# airsensor.net
KiCad netlist of a schematic drawn in Altium Designer
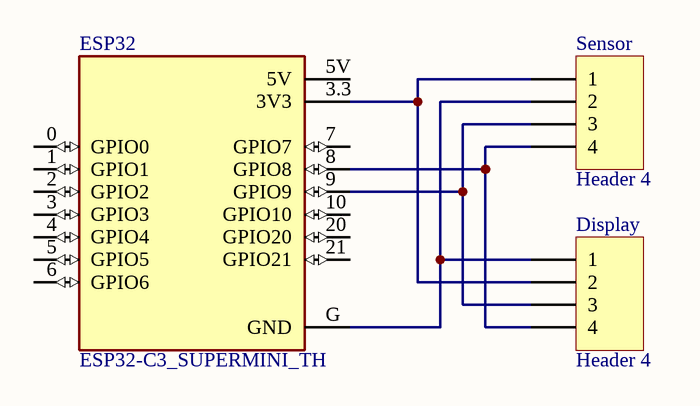
[diagram p0: airsensor.SchDoc]

(export (version "E")
  (design (tool "Eeschema 10.0.6"))
  (components
    (comp (ref "Display")
      (value "Header 4")
      (footprint "HDR1X4")
      (description "Header, 4-Pin")
      (fields (field (name "PUBLISHER") "Altium Limited"))
      (libsource (lib "Miscellaneous Connectors") (part "Header 4"))
    )
    (comp (ref "ESP32")
      (value "ESP32-C3_SUPERMINI_TH")
      (footprint "MODULE_ESP32-C3_SUPERMINI")
      (description "Super tiny ESP32-C3 board")
      (fields (field (name "MF") "Espressif Systems") (field (name "MP") "ESP32-C3 SuperMini_TH"))
      (libsource (lib "ESP32-C3_SUPERMINI_TH") (part "ESP32-C3_SUPERMINI_TH"))
    )
    (comp (ref "Sensor")
      (value "Header 4")
      (footprint "HDR1X4")
      (description "Header, 4-Pin")
      (fields (field (name "PUBLISHER") "Altium Limited"))
      (libsource (lib "Miscellaneous Connectors") (part "Header 4"))
    )
  )
  (nets
    (net (code "1") (name "Net-(ESP32-3V3)") (class "Default")
      (node (ref "Display") (pin "2") (pinfunction "2_2") (pintype "passive"))
      (node (ref "ESP32") (pin "3.3") (pinfunction "3V3_3.3") (pintype "power_in"))
      (node (ref "Sensor") (pin "1") (pinfunction "1_1") (pintype "passive"))
    )
    (net (code "2") (name "Net-(ESP32-GND)") (class "Default")
      (node (ref "Display") (pin "1") (pinfunction "1_1") (pintype "passive"))
      (node (ref "ESP32") (pin "G") (pinfunction "GND_G") (pintype "power_in"))
      (node (ref "Sensor") (pin "2") (pinfunction "2_2") (pintype "passive"))
    )
    (net (code "3") (name "Net-(ESP32-GPIO8)") (class "Default")
      (node (ref "Display") (pin "4") (pinfunction "4_4") (pintype "passive"))
      (node (ref "ESP32") (pin "8") (pinfunction "GPIO8_8") (pintype "bidirectional"))
      (node (ref "Sensor") (pin "4") (pinfunction "4_4") (pintype "passive"))
    )
    (net (code "4") (name "Net-(ESP32-GPIO9)") (class "Default")
      (node (ref "Display") (pin "3") (pinfunction "3_3") (pintype "passive"))
      (node (ref "ESP32") (pin "9") (pinfunction "GPIO9_9") (pintype "bidirectional"))
      (node (ref "Sensor") (pin "3") (pinfunction "3_3") (pintype "passive"))
    )
    (net (code "5") (name "unconnected-(ESP32-GPIO0-Pad0)") (class "Default")
      (node (ref "ESP32") (pin "0") (pinfunction "GPIO0_0") (pintype "bidirectional"))
    )
    (net (code "6") (name "unconnected-(ESP32-GPIO1-Pad1)") (class "Default")
      (node (ref "ESP32") (pin "1") (pinfunction "GPIO1_1") (pintype "bidirectional"))
    )
    (net (code "7") (name "unconnected-(ESP32-GPIO2-Pad2)") (class "Default")
      (node (ref "ESP32") (pin "2") (pinfunction "GPIO2_2") (pintype "bidirectional"))
    )
    (net (code "8") (name "unconnected-(ESP32-GPIO3-Pad3)") (class "Default")
      (node (ref "ESP32") (pin "3") (pinfunction "GPIO3_3") (pintype "bidirectional"))
    )
    (net (code "9") (name "unconnected-(ESP32-GPIO4-Pad4)") (class "Default")
      (node (ref "ESP32") (pin "4") (pinfunction "GPIO4_4") (pintype "bidirectional"))
    )
    (net (code "10") (name "unconnected-(ESP32-GPIO5-Pad5)") (class "Default")
      (node (ref "ESP32") (pin "5") (pinfunction "GPIO5_5") (pintype "bidirectional"))
    )
    (net (code "11") (name "unconnected-(ESP32-GPIO6-Pad6)") (class "Default")
      (node (ref "ESP32") (pin "6") (pinfunction "GPIO6_6") (pintype "bidirectional"))
    )
    (net (code "12") (name "unconnected-(ESP32-GPIO7-Pad7)") (class "Default")
      (node (ref "ESP32") (pin "7") (pinfunction "GPIO7_7") (pintype "bidirectional"))
    )
    (net (code "13") (name "unconnected-(ESP32-GPIO10-Pad10)") (class "Default")
      (node (ref "ESP32") (pin "10") (pinfunction "GPIO10_10") (pintype "bidirectional"))
    )
    (net (code "14") (name "unconnected-(ESP32-GPIO20-Pad20)") (class "Default")
      (node (ref "ESP32") (pin "20") (pinfunction "GPIO20_20") (pintype "bidirectional"))
    )
    (net (code "15") (name "unconnected-(ESP32-GPIO21-Pad21)") (class "Default")
      (node (ref "ESP32") (pin "21") (pinfunction "GPIO21_21") (pintype "bidirectional"))
    )
    (net (code "16") (name "unconnected-(ESP32-Pad5V)") (class "Default")
      (node (ref "ESP32") (pin "5V") (pinfunction "5V_5V") (pintype "power_in"))
    )
  )
)
